# Leds.net
KiCad netlist of a schematic drawn in Altium Designer
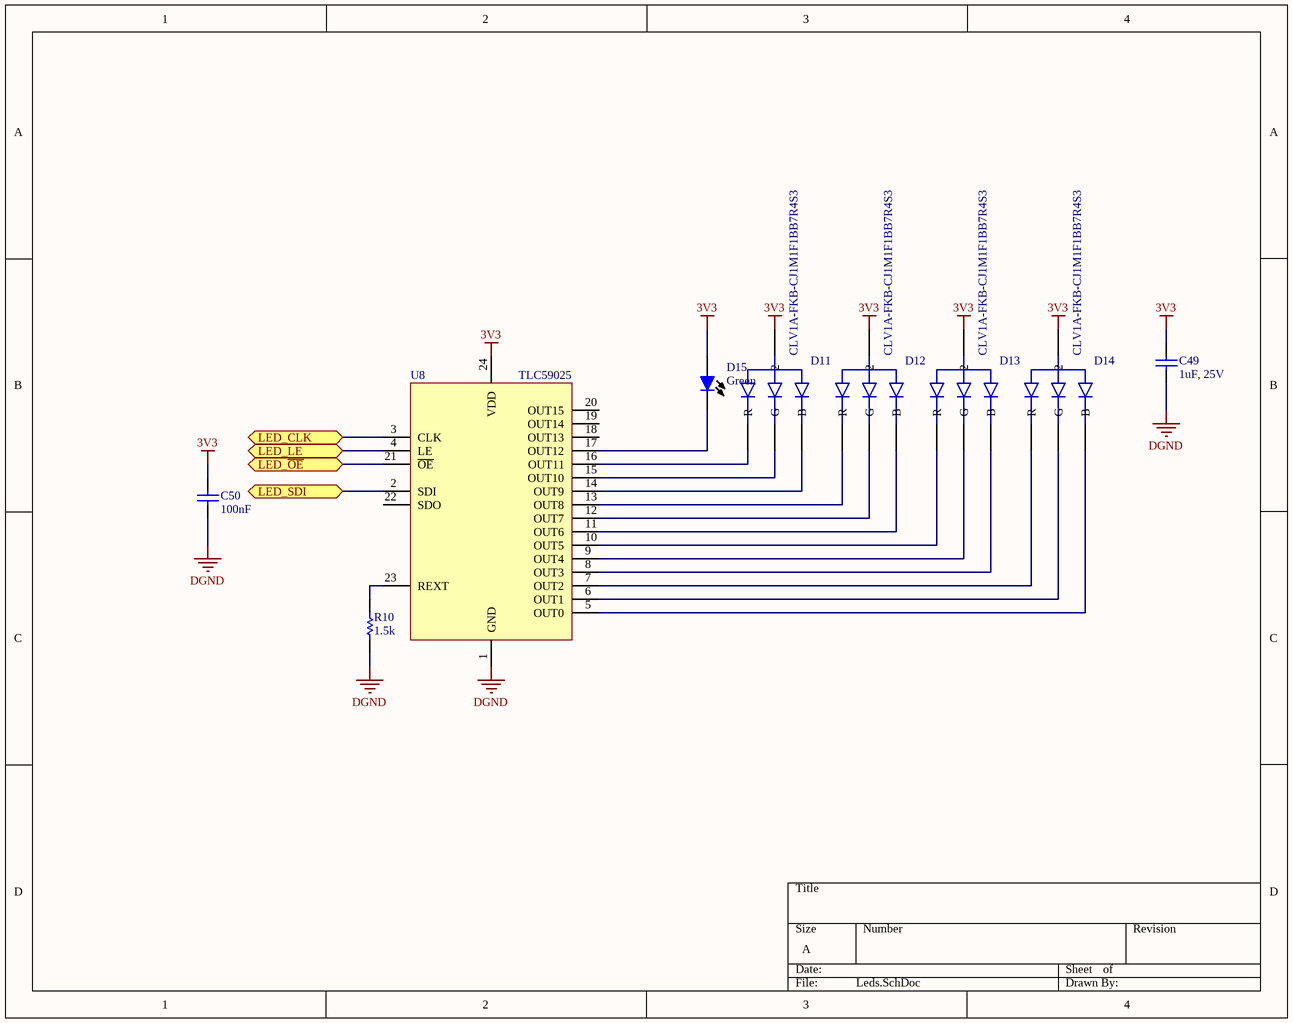
[diagram p0: Leds.SchDoc]

(export (version "E")
  (design (tool "Eeschema 10.0.6"))
  (components
    (comp (ref "C49")
      (value "1uF, 25V")
      (footprint "CAPC1608L")
      (description "Capacitor (Semiconductor SIM Model)")
      (fields (field (name "PUBLISHER") "Altium Limited"))
      (libsource (lib "Miscellaneous Devices") (part "Cap Semi"))
    )
    (comp (ref "C50")
      (value "100nF")
      (footprint "CAPC1608L")
      (description "Capacitor (Semiconductor SIM Model)")
      (fields (field (name "PUBLISHER") "Altium Limited"))
      (libsource (lib "Miscellaneous Devices") (part "Cap Semi"))
    )
    (comp (ref "D11")
      (value "CLV1A-FKB-CJ1M1F1BB7R4S3")
      (footprint "RGB_LED_PLCC4")
      (libsource (lib "New_library") (part "RGB_LED_COMMON_ANODE"))
    )
    (comp (ref "D12")
      (value "CLV1A-FKB-CJ1M1F1BB7R4S3")
      (footprint "RGB_LED_PLCC4")
      (libsource (lib "New_library") (part "RGB_LED_COMMON_ANODE"))
    )
    (comp (ref "D13")
      (value "CLV1A-FKB-CJ1M1F1BB7R4S3")
      (footprint "RGB_LED_PLCC4")
      (libsource (lib "New_library") (part "RGB_LED_COMMON_ANODE"))
    )
    (comp (ref "D14")
      (value "CLV1A-FKB-CJ1M1F1BB7R4S3")
      (footprint "RGB_LED_PLCC4")
      (libsource (lib "New_library") (part "RGB_LED_COMMON_ANODE"))
    )
    (comp (ref "D15")
      (value "LED Green")
      (footprint "CD1608-0603")
      (description "LED")
      (fields (field (name "COLOR") "Green"))
      (libsource (lib "Roombots") (part "LED"))
    )
    (comp (ref "R10")
      (value "1.5k")
      (footprint "RESC1608L")
      (description "Semiconductor Resistor")
      (fields (field (name "PUBLISHER") "Altium Limited"))
      (libsource (lib "Miscellaneous Devices") (part "Res Semi"))
    )
    (comp (ref "U8") (value "TLC59025") (footprint "SOP24") (libsource (lib "New_library") (part "TLC59025")))
  )
  (nets
    (net (code "1") (name "/LED_CLK") (class "Default")
      (node (ref "U8") (pin "3") (pinfunction "CLK_3") (pintype "passive"))
    )
    (net (code "2") (name "/LED_LE") (class "Default")
      (node (ref "U8") (pin "4") (pinfunction "LE_4") (pintype "passive"))
    )
    (net (code "3") (name "/LED_SDI") (class "Default")
      (node (ref "U8") (pin "2") (pinfunction "SDI_2") (pintype "passive"))
    )
    (net (code "4") (name "/LED_~{OE}") (class "Default")
      (node (ref "U8") (pin "21") (pinfunction "~{OE}_21") (pintype "passive"))
    )
    (net (code "5") (name "3V3") (class "Default")
      (node (ref "C49") (pin "2") (pinfunction "2_2") (pintype "passive"))
      (node (ref "C50") (pin "2") (pinfunction "2_2") (pintype "passive"))
      (node (ref "D11") (pin "2") (pinfunction "2_2") (pintype "passive"))
      (node (ref "D12") (pin "2") (pinfunction "2_2") (pintype "passive"))
      (node (ref "D13") (pin "2") (pinfunction "2_2") (pintype "passive"))
      (node (ref "D14") (pin "2") (pinfunction "2_2") (pintype "passive"))
      (node (ref "D15") (pin "1") (pinfunction "A_1") (pintype "passive"))
      (node (ref "U8") (pin "24") (pinfunction "VDD_24") (pintype "power_in"))
    )
    (net (code "6") (name "DGND") (class "Default")
      (node (ref "C49") (pin "1") (pinfunction "1_1") (pintype "passive"))
      (node (ref "C50") (pin "1") (pinfunction "1_1") (pintype "passive"))
      (node (ref "R10") (pin "1") (pinfunction "1_1") (pintype "passive"))
      (node (ref "U8") (pin "1") (pinfunction "GND_1") (pintype "power_in"))
    )
    (net (code "7") (name "Net-(D11-B)") (class "Default")
      (node (ref "D11") (pin "3") (pinfunction "B_3") (pintype "passive"))
      (node (ref "U8") (pin "14") (pinfunction "OUT9_14") (pintype "passive"))
    )
    (net (code "8") (name "Net-(D11-G)") (class "Default")
      (node (ref "D11") (pin "4") (pinfunction "G_4") (pintype "passive"))
      (node (ref "U8") (pin "15") (pinfunction "OUT10_15") (pintype "passive"))
    )
    (net (code "9") (name "Net-(D11-R)") (class "Default")
      (node (ref "D11") (pin "1") (pinfunction "R_1") (pintype "passive"))
      (node (ref "U8") (pin "16") (pinfunction "OUT11_16") (pintype "passive"))
    )
    (net (code "10") (name "Net-(D12-B)") (class "Default")
      (node (ref "D12") (pin "3") (pinfunction "B_3") (pintype "passive"))
      (node (ref "U8") (pin "11") (pinfunction "OUT6_11") (pintype "passive"))
    )
    (net (code "11") (name "Net-(D12-G)") (class "Default")
      (node (ref "D12") (pin "4") (pinfunction "G_4") (pintype "passive"))
      (node (ref "U8") (pin "12") (pinfunction "OUT7_12") (pintype "passive"))
    )
    (net (code "12") (name "Net-(D12-R)") (class "Default")
      (node (ref "D12") (pin "1") (pinfunction "R_1") (pintype "passive"))
      (node (ref "U8") (pin "13") (pinfunction "OUT8_13") (pintype "power_in"))
    )
    (net (code "13") (name "Net-(D13-B)") (class "Default")
      (node (ref "D13") (pin "3") (pinfunction "B_3") (pintype "passive"))
      (node (ref "U8") (pin "8") (pinfunction "OUT3_8") (pintype "power_in"))
    )
    (net (code "14") (name "Net-(D13-G)") (class "Default")
      (node (ref "D13") (pin "4") (pinfunction "G_4") (pintype "passive"))
      (node (ref "U8") (pin "9") (pinfunction "OUT4_9") (pintype "passive"))
    )
    (net (code "15") (name "Net-(D13-R)") (class "Default")
      (node (ref "D13") (pin "1") (pinfunction "R_1") (pintype "passive"))
      (node (ref "U8") (pin "10") (pinfunction "OUT5_10") (pintype "passive"))
    )
    (net (code "16") (name "Net-(D14-B)") (class "Default")
      (node (ref "D14") (pin "3") (pinfunction "B_3") (pintype "passive"))
      (node (ref "U8") (pin "5") (pinfunction "OUT0_5") (pintype "passive"))
    )
    (net (code "17") (name "Net-(D14-G)") (class "Default")
      (node (ref "D14") (pin "4") (pinfunction "G_4") (pintype "passive"))
      (node (ref "U8") (pin "6") (pinfunction "OUT1_6") (pintype "passive"))
    )
    (net (code "18") (name "Net-(D14-R)") (class "Default")
      (node (ref "D14") (pin "1") (pinfunction "R_1") (pintype "passive"))
      (node (ref "U8") (pin "7") (pinfunction "OUT2_7") (pintype "passive"))
    )
    (net (code "19") (name "Net-(D15-C)") (class "Default")
      (node (ref "D15") (pin "2") (pinfunction "C_2") (pintype "passive"))
      (node (ref "U8") (pin "17") (pinfunction "OUT12_17") (pintype "passive"))
    )
    (net (code "20") (name "Net-(U8-REXT)") (class "Default")
      (node (ref "R10") (pin "2") (pinfunction "2_2") (pintype "passive"))
      (node (ref "U8") (pin "23") (pinfunction "REXT_23") (pintype "passive"))
    )
    (net (code "21") (name "unconnected-(U8-OUT13-Pad18)") (class "Default")
      (node (ref "U8") (pin "18") (pinfunction "OUT13_18") (pintype "passive"))
    )
    (net (code "22") (name "unconnected-(U8-OUT14-Pad19)") (class "Default")
      (node (ref "U8") (pin "19") (pinfunction "OUT14_19") (pintype "power_in"))
    )
    (net (code "23") (name "unconnected-(U8-OUT15-Pad20)") (class "Default")
      (node (ref "U8") (pin "20") (pinfunction "OUT15_20") (pintype "passive"))
    )
    (net (code "24") (name "unconnected-(U8-SDO-Pad22)") (class "Default")
      (node (ref "U8") (pin "22") (pinfunction "SDO_22") (pintype "passive"))
    )
  )
)
